# esp07_prog.net
KiCad netlist of a schematic drawn in EAGLE
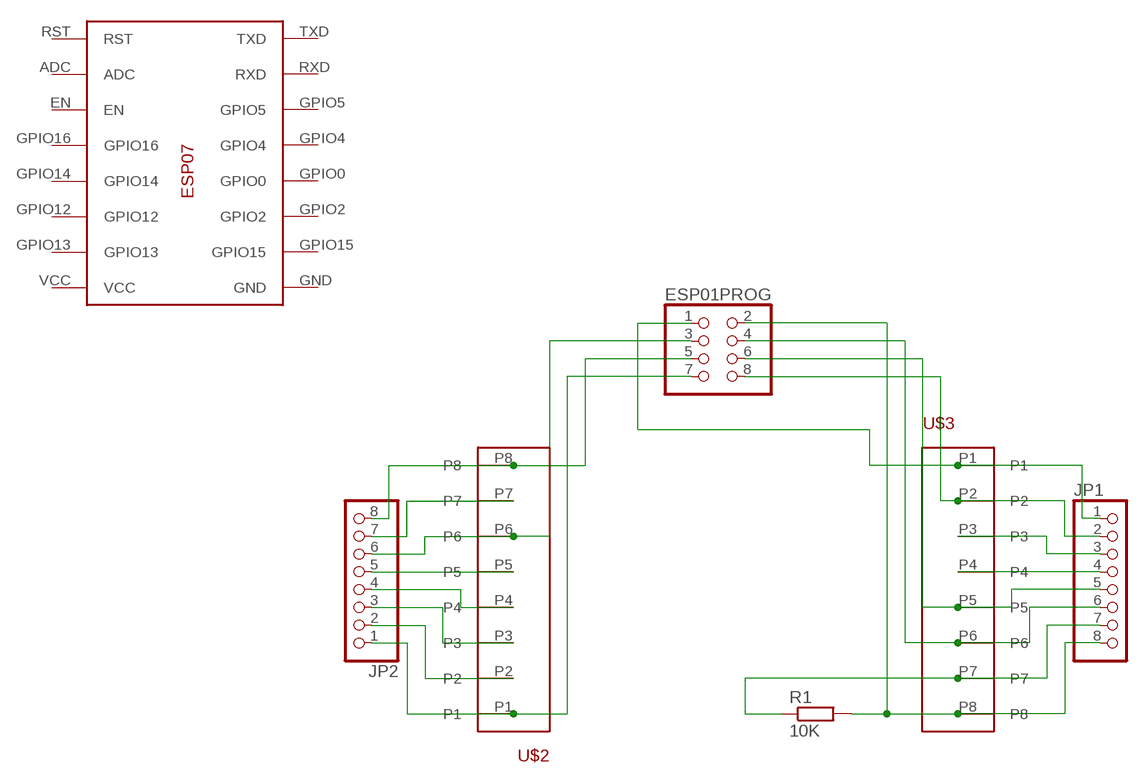
[diagram p0: schematic, sheet 1]

(export (version "E")
  (design (tool "Eeschema 10.0.6"))
  (components
    (comp (ref "ESP01PROG")
      (value "PINHD-2X4")
      (footprint "eagle-import:2X04")
      (libsource (lib "eagle-import") (part "PINHD-2X4"))
    )
    (comp (ref "JP1")
      (value "PINHD-1X8")
      (footprint "eagle-import:1X08")
      (libsource (lib "eagle-import") (part "PINHD-1X8"))
    )
    (comp (ref "JP2")
      (value "PINHD-1X8")
      (footprint "eagle-import:1X08")
      (libsource (lib "eagle-import") (part "PINHD-1X8"))
    )
    (comp (ref "R1")
      (value "10K")
      (footprint "eagle-import:0204_7")
      (libsource (lib "eagle-import") (part "R-EU_0204/7"))
    )
    (comp (ref "U$1")
      (value "ESP07")
      (footprint "eagle-import:ESP07")
      (libsource (lib "eagle-import") (part "ESP07"))
    )
    (comp (ref "U$2")
      (value "PINHD8X2MM")
      (footprint "eagle-import:PINHD8X2MM")
      (libsource (lib "eagle-import") (part "PINHD8X2MM"))
    )
    (comp (ref "U$3")
      (value "PINHD8X2MM")
      (footprint "eagle-import:PINHD8X2MM")
      (libsource (lib "eagle-import") (part "PINHD8X2MM"))
    )
  )
  (nets
    (net (code "1") (name "Net-(ESP01PROG-Pad1)") (class "Default")
      (node (ref "ESP01PROG") (pin "1") (pinfunction "1_1") (pintype "passive"))
      (node (ref "JP1") (pin "1") (pinfunction "1_1") (pintype "passive"))
      (node (ref "U$3") (pin "P1") (pinfunction "P1_P1") (pintype "bidirectional"))
    )
    (net (code "2") (name "Net-(ESP01PROG-Pad2)") (class "Default")
      (node (ref "ESP01PROG") (pin "2") (pinfunction "2_2") (pintype "passive"))
      (node (ref "JP1") (pin "8") (pinfunction "8_8") (pintype "passive"))
      (node (ref "R1") (pin "2") (pinfunction "2_2") (pintype "passive"))
      (node (ref "U$3") (pin "P8") (pinfunction "P8_P8") (pintype "bidirectional"))
    )
    (net (code "3") (name "Net-(ESP01PROG-Pad3)") (class "Default")
      (node (ref "ESP01PROG") (pin "3") (pinfunction "3_3") (pintype "passive"))
      (node (ref "JP2") (pin "6") (pinfunction "6_6") (pintype "passive"))
      (node (ref "U$2") (pin "P6") (pinfunction "P6_P6") (pintype "bidirectional"))
    )
    (net (code "4") (name "Net-(ESP01PROG-Pad4)") (class "Default")
      (node (ref "ESP01PROG") (pin "4") (pinfunction "4_4") (pintype "passive"))
      (node (ref "JP1") (pin "6") (pinfunction "6_6") (pintype "passive"))
      (node (ref "U$3") (pin "P6") (pinfunction "P6_P6") (pintype "bidirectional"))
    )
    (net (code "5") (name "Net-(ESP01PROG-Pad5)") (class "Default")
      (node (ref "ESP01PROG") (pin "5") (pinfunction "5_5") (pintype "passive"))
      (node (ref "JP2") (pin "8") (pinfunction "8_8") (pintype "passive"))
      (node (ref "U$2") (pin "P8") (pinfunction "P8_P8") (pintype "bidirectional"))
    )
    (net (code "6") (name "Net-(ESP01PROG-Pad6)") (class "Default")
      (node (ref "ESP01PROG") (pin "6") (pinfunction "6_6") (pintype "passive"))
      (node (ref "JP1") (pin "5") (pinfunction "5_5") (pintype "passive"))
      (node (ref "U$3") (pin "P5") (pinfunction "P5_P5") (pintype "bidirectional"))
    )
    (net (code "7") (name "Net-(ESP01PROG-Pad7)") (class "Default")
      (node (ref "ESP01PROG") (pin "7") (pinfunction "7_7") (pintype "passive"))
      (node (ref "JP2") (pin "1") (pinfunction "1_1") (pintype "passive"))
      (node (ref "U$2") (pin "P1") (pinfunction "P1_P1") (pintype "bidirectional"))
    )
    (net (code "8") (name "Net-(ESP01PROG-Pad8)") (class "Default")
      (node (ref "ESP01PROG") (pin "8") (pinfunction "8_8") (pintype "passive"))
      (node (ref "JP1") (pin "2") (pinfunction "2_2") (pintype "passive"))
      (node (ref "U$3") (pin "P2") (pinfunction "P2_P2") (pintype "bidirectional"))
    )
    (net (code "9") (name "Net-(JP1-Pad3)") (class "Default")
      (node (ref "JP1") (pin "3") (pinfunction "3_3") (pintype "passive"))
      (node (ref "U$3") (pin "P3") (pinfunction "P3_P3") (pintype "bidirectional"))
    )
    (net (code "10") (name "Net-(JP1-Pad4)") (class "Default")
      (node (ref "JP1") (pin "4") (pinfunction "4_4") (pintype "passive"))
      (node (ref "U$3") (pin "P4") (pinfunction "P4_P4") (pintype "bidirectional"))
    )
    (net (code "11") (name "Net-(JP1-Pad7)") (class "Default")
      (node (ref "JP1") (pin "7") (pinfunction "7_7") (pintype "passive"))
      (node (ref "R1") (pin "1") (pinfunction "1_1") (pintype "passive"))
      (node (ref "U$3") (pin "P7") (pinfunction "P7_P7") (pintype "bidirectional"))
    )
    (net (code "12") (name "Net-(JP2-Pad2)") (class "Default")
      (node (ref "JP2") (pin "2") (pinfunction "2_2") (pintype "passive"))
      (node (ref "U$2") (pin "P2") (pinfunction "P2_P2") (pintype "bidirectional"))
    )
    (net (code "13") (name "Net-(JP2-Pad3)") (class "Default")
      (node (ref "JP2") (pin "3") (pinfunction "3_3") (pintype "passive"))
      (node (ref "U$2") (pin "P3") (pinfunction "P3_P3") (pintype "bidirectional"))
    )
    (net (code "14") (name "Net-(JP2-Pad4)") (class "Default")
      (node (ref "JP2") (pin "4") (pinfunction "4_4") (pintype "passive"))
      (node (ref "U$2") (pin "P4") (pinfunction "P4_P4") (pintype "bidirectional"))
    )
    (net (code "15") (name "Net-(JP2-Pad5)") (class "Default")
      (node (ref "JP2") (pin "5") (pinfunction "5_5") (pintype "passive"))
      (node (ref "U$2") (pin "P5") (pinfunction "P5_P5") (pintype "bidirectional"))
    )
    (net (code "16") (name "Net-(JP2-Pad7)") (class "Default")
      (node (ref "JP2") (pin "7") (pinfunction "7_7") (pintype "passive"))
      (node (ref "U$2") (pin "P7") (pinfunction "P7_P7") (pintype "bidirectional"))
    )
    (net (code "17") (name "unconnected-(U$1-PadADC)") (class "Default")
      (node (ref "U$1") (pin "ADC") (pinfunction "ADC_ADC") (pintype "bidirectional"))
    )
    (net (code "18") (name "unconnected-(U$1-PadEN)") (class "Default")
      (node (ref "U$1") (pin "EN") (pinfunction "EN_EN") (pintype "bidirectional"))
    )
    (net (code "19") (name "unconnected-(U$1-PadGND)") (class "Default")
      (node (ref "U$1") (pin "GND") (pinfunction "GND_GND") (pintype "bidirectional"))
    )
    (net (code "20") (name "unconnected-(U$1-PadGPIO0)") (class "Default")
      (node (ref "U$1") (pin "GPIO0") (pinfunction "GPIO0_GPIO0") (pintype "bidirectional"))
    )
    (net (code "21") (name "unconnected-(U$1-PadGPIO2)") (class "Default")
      (node (ref "U$1") (pin "GPIO2") (pinfunction "GPIO2_GPIO2") (pintype "bidirectional"))
    )
    (net (code "22") (name "unconnected-(U$1-PadGPIO4)") (class "Default")
      (node (ref "U$1") (pin "GPIO4") (pinfunction "GPIO4_GPIO4") (pintype "bidirectional"))
    )
    (net (code "23") (name "unconnected-(U$1-PadGPIO5)") (class "Default")
      (node (ref "U$1") (pin "GPIO5") (pinfunction "GPIO5_GPIO5") (pintype "bidirectional"))
    )
    (net (code "24") (name "unconnected-(U$1-PadGPIO12)") (class "Default")
      (node (ref "U$1") (pin "GPIO12") (pinfunction "GPIO12_GPIO12") (pintype "bidirectional"))
    )
    (net (code "25") (name "unconnected-(U$1-PadGPIO13)") (class "Default")
      (node (ref "U$1") (pin "GPIO13") (pinfunction "GPIO13_GPIO13") (pintype "bidirectional"))
    )
    (net (code "26") (name "unconnected-(U$1-PadGPIO14)") (class "Default")
      (node (ref "U$1") (pin "GPIO14") (pinfunction "GPIO14_GPIO14") (pintype "bidirectional"))
    )
    (net (code "27") (name "unconnected-(U$1-PadGPIO15)") (class "Default")
      (node (ref "U$1") (pin "GPIO15") (pinfunction "GPIO15_GPIO15") (pintype "bidirectional"))
    )
    (net (code "28") (name "unconnected-(U$1-PadGPIO16)") (class "Default")
      (node (ref "U$1") (pin "GPIO16") (pinfunction "GPIO16_GPIO16") (pintype "bidirectional"))
    )
    (net (code "29") (name "unconnected-(U$1-PadRST)") (class "Default")
      (node (ref "U$1") (pin "RST") (pinfunction "RST_RST") (pintype "bidirectional"))
    )
    (net (code "30") (name "unconnected-(U$1-PadRXD)") (class "Default")
      (node (ref "U$1") (pin "RXD") (pinfunction "RXD_RXD") (pintype "bidirectional"))
    )
    (net (code "31") (name "unconnected-(U$1-PadTXD)") (class "Default")
      (node (ref "U$1") (pin "TXD") (pinfunction "TXD_TXD") (pintype "bidirectional"))
    )
    (net (code "32") (name "unconnected-(U$1-PadVCC)") (class "Default")
      (node (ref "U$1") (pin "VCC") (pinfunction "VCC_VCC") (pintype "bidirectional"))
    )
  )
)
